# USB.net
KiCad netlist of a schematic drawn in Altium Designer
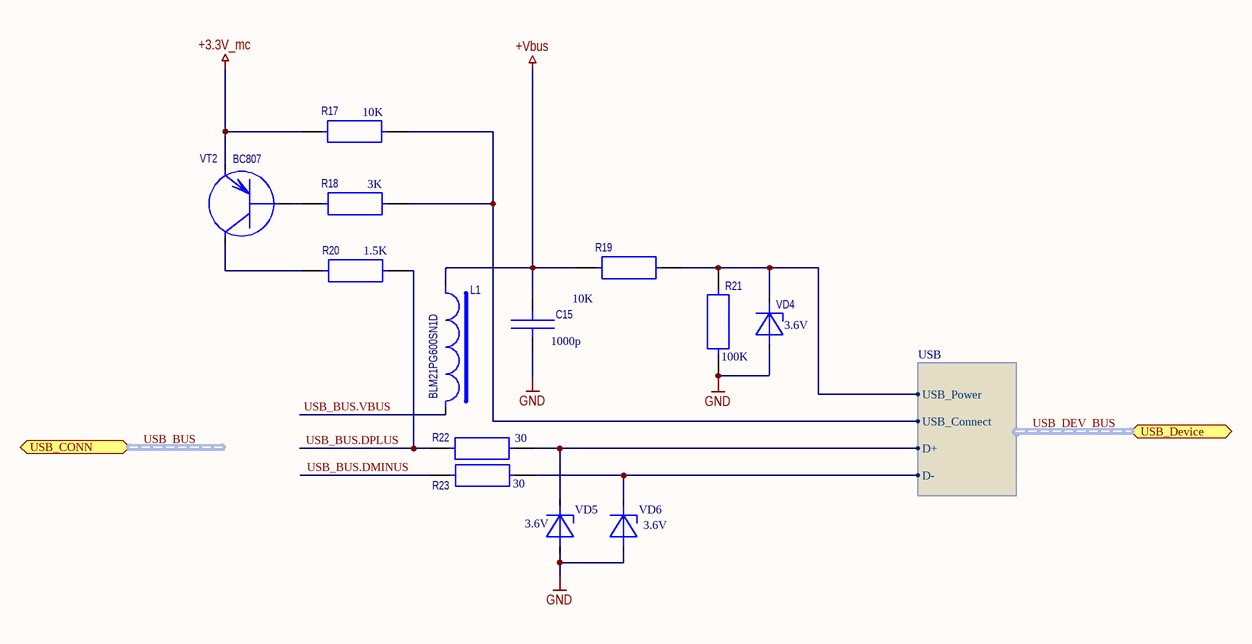
[diagram p0: USB.SchDoc]

(export (version "E")
  (design (tool "Eeschema 10.0.6"))
  (components
    (comp (ref "C15")
      (value "1000p")
      (footprint "0603C")
      (description "Конденсатор обыкновенный")
      (libsource (lib "Discrete") (part "CAP"))
    )
    (comp (ref "L1")
      (value "BLM21PG600SN1D")
      (footprint "0805")
      (description "Индуктивность")
      (libsource (lib "Discrete") (part "INDUCTOR_"))
    )
    (comp (ref "R17")
      (value "10K")
      (footprint "0603R")
      (description "Резистор обыкновенный")
      (libsource (lib "Discrete") (part "RES"))
    )
    (comp (ref "R18")
      (value "3K")
      (footprint "0603R")
      (description "Резистор обыкновенный")
      (libsource (lib "Discrete") (part "RES"))
    )
    (comp (ref "R19")
      (value "10K")
      (footprint "0603R")
      (description "Резистор обыкновенный")
      (libsource (lib "Discrete") (part "RES"))
    )
    (comp (ref "R20")
      (value "1.5K")
      (footprint "0603R")
      (description "Резистор обыкновенный")
      (libsource (lib "Discrete") (part "RES"))
    )
    (comp (ref "R21")
      (value "100K")
      (footprint "0603R")
      (description "Резистор обыкновенный")
      (libsource (lib "Discrete") (part "RES"))
    )
    (comp (ref "R22")
      (value "30")
      (footprint "0603R")
      (description "Резистор обыкновенный")
      (libsource (lib "Discrete") (part "RES"))
    )
    (comp (ref "R23")
      (value "30")
      (footprint "0603R")
      (description "Резистор обыкновенный")
      (libsource (lib "Discrete") (part "RES"))
    )
    (comp (ref "VD4")
      (value "3.6V")
      (footprint "SOT23_1DIODE")
      (description "Стабилитрон")
      (fields (field (name "Comment") "BZX84C3V6"))
      (libsource (lib "Discrete") (part "ZENNER"))
    )
    (comp (ref "VD5")
      (value "3.6V")
      (footprint "SOT23_1DIODE")
      (description "Стабилитрон")
      (fields (field (name "Comment") "BZX84C3V6"))
      (libsource (lib "Discrete") (part "ZENNER"))
    )
    (comp (ref "VD6")
      (value "3.6V")
      (footprint "SOT23_1DIODE")
      (description "Стабилитрон")
      (fields (field (name "Comment") "BZX84C3V6"))
      (libsource (lib "Discrete") (part "ZENNER"))
    )
    (comp (ref "VT2")
      (value "BC807")
      (footprint "SOT95P230X110-3L")
      (description "Биполярный PNP транзистор")
      (libsource (lib "Discrete") (part "SOT32_PNP"))
    )
  )
  (nets
    (net (code "3") (name "+3.3V_mc") (class "Default")
      (node (ref "R17") (pin "2") (pinfunction "2_2") (pintype "passive"))
      (node (ref "VT2") (pin "2") (pinfunction "E_2") (pintype "passive"))
    )
    (net (code "4") (name "+Vbus") (class "Default")
      (node (ref "C15") (pin "2") (pinfunction "2_2") (pintype "passive"))
      (node (ref "L1") (pin "1") (pinfunction "1_1") (pintype "passive"))
      (node (ref "R19") (pin "2") (pinfunction "2_2") (pintype "passive"))
    )
    (net (code "5") (name "/USB_BUS.DMINUS") (class "Default")
      (node (ref "R23") (pin "1") (pinfunction "1_1") (pintype "passive"))
    )
    (net (code "6") (name "/USB_BUS.DPLUS") (class "Default")
      (node (ref "R20") (pin "1") (pinfunction "1_1") (pintype "passive"))
      (node (ref "R22") (pin "1") (pinfunction "1_1") (pintype "passive"))
    )
    (net (code "7") (name "/USB_BUS.VBUS") (class "Default")
      (node (ref "L1") (pin "2") (pinfunction "2_2") (pintype "passive"))
    )
    (net (code "10") (name "GND") (class "Default")
      (node (ref "C15") (pin "1") (pinfunction "1_1") (pintype "passive"))
      (node (ref "R21") (pin "1") (pinfunction "1_1") (pintype "passive"))
      (node (ref "VD4") (pin "A") (pinfunction "A_A") (pintype "passive"))
      (node (ref "VD5") (pin "A") (pinfunction "A_A") (pintype "passive"))
      (node (ref "VD6") (pin "A") (pinfunction "A_A") (pintype "passive"))
    )
    (net (code "11") (name "Net-(R17-Pad1)") (class "Default")
      (node (ref "R17") (pin "1") (pinfunction "1_1") (pintype "passive"))
      (node (ref "R18") (pin "1") (pinfunction "1_1") (pintype "passive"))
    )
    (net (code "12") (name "Net-(R19-Pad1)") (class "Default")
      (node (ref "R19") (pin "1") (pinfunction "1_1") (pintype "passive"))
      (node (ref "R21") (pin "2") (pinfunction "2_2") (pintype "passive"))
      (node (ref "VD4") (pin "K") (pinfunction "K_K") (pintype "passive"))
    )
    (net (code "13") (name "Net-(R22-Pad2)") (class "Default")
      (node (ref "R22") (pin "2") (pinfunction "2_2") (pintype "passive"))
      (node (ref "VD5") (pin "K") (pinfunction "K_K") (pintype "passive"))
    )
    (net (code "14") (name "Net-(R23-Pad2)") (class "Default")
      (node (ref "R23") (pin "2") (pinfunction "2_2") (pintype "passive"))
      (node (ref "VD6") (pin "K") (pinfunction "K_K") (pintype "passive"))
    )
    (net (code "15") (name "Net-(VT2-B)") (class "Default")
      (node (ref "R18") (pin "2") (pinfunction "2_2") (pintype "passive"))
      (node (ref "VT2") (pin "1") (pinfunction "B_1") (pintype "passive"))
    )
    (net (code "16") (name "Net-(VT2-C)") (class "Default")
      (node (ref "R20") (pin "2") (pinfunction "2_2") (pintype "passive"))
      (node (ref "VT2") (pin "3") (pinfunction "C_3") (pintype "passive"))
    )
  )
)
